# TI_DMM_PCB.net
KiCad netlist of a schematic drawn in EAGLE
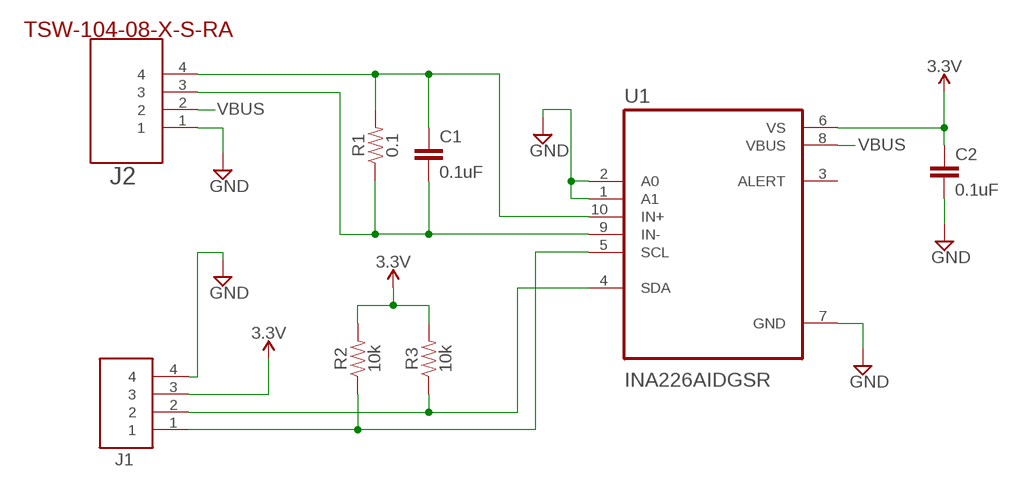
[diagram p0: schematic, sheet 1]

(export (version "E")
  (design (tool "Eeschema 10.0.6"))
  (components
    (comp (ref "C1")
      (value "0.1uF")
      (footprint "eagle-import:0603")
      (libsource (lib "eagle-import") (part "0.1UF-0603"))
    )
    (comp (ref "C2")
      (value "0.1uF")
      (footprint "eagle-import:0603")
      (libsource (lib "eagle-import") (part "0.1UF-0603"))
    )
    (comp (ref "J1")
      (value "4PIN_GROVE_CONNECTOR")
      (footprint "eagle-import:SEEED_114020163")
      (fields (field (name "MF") "Seeed Technology Co., Ltd") (field (name "MP") "110990030"))
      (libsource (lib "eagle-import") (part "4PIN_GROVE_CONNECTOR"))
    )
    (comp (ref "J2")
      (value "TSW-104-08-X-S-RAJ")
      (footprint "eagle-import:SAMTEC-TSW-104-08-X-S-RA")
      (fields (field (name "MF") "Samtec") (field (name "MP") "TSW-104-08-T-S-RA"))
      (libsource (lib "eagle-import") (part "TSW-104-08-X-S-RAJ"))
    )
    (comp (ref "R1")
      (value "0.1")
      (footprint "eagle-import:0603")
      (libsource (lib "eagle-import") (part "0.1OHM"))
    )
    (comp (ref "R2")
      (value "10k")
      (footprint "eagle-import:0603")
      (libsource (lib "eagle-import") (part "10KOHM-0603"))
    )
    (comp (ref "R3")
      (value "10k")
      (footprint "eagle-import:0603")
      (libsource (lib "eagle-import") (part "10KOHM-0603"))
    )
    (comp (ref "U1")
      (value "INA226AIDGSR")
      (footprint "eagle-import:SOP50P490X110-10N")
      (fields (field (name "MF") "Texas Instruments"))
      (libsource (lib "eagle-import") (part "INA226AIDGSR"))
    )
  )
  (nets
    (net (code "1") (name "/VBUS") (class "Default")
      (node (ref "J2") (pin "2") (pinfunction "2_2") (pintype "bidirectional"))
      (node (ref "U1") (pin "8") (pinfunction "VBUS_8") (pintype "power_in"))
    )
    (net (code "2") (name "3.3V") (class "Default")
      (node (ref "C2") (pin "1") (pinfunction "1_1") (pintype "passive"))
      (node (ref "J1") (pin "3") (pinfunction "3_3") (pintype "passive"))
      (node (ref "R2") (pin "2") (pinfunction "2_2") (pintype "passive"))
      (node (ref "R3") (pin "2") (pinfunction "2_2") (pintype "passive"))
      (node (ref "U1") (pin "6") (pinfunction "VS_6") (pintype "power_in"))
    )
    (net (code "3") (name "GND") (class "Default")
      (node (ref "C2") (pin "2") (pinfunction "2_2") (pintype "passive"))
      (node (ref "J1") (pin "4") (pinfunction "4_4") (pintype "passive"))
      (node (ref "J2") (pin "1") (pinfunction "1_1") (pintype "bidirectional"))
      (node (ref "U1") (pin "1") (pinfunction "A1_1") (pintype "input"))
      (node (ref "U1") (pin "2") (pinfunction "A0_2") (pintype "input"))
      (node (ref "U1") (pin "7") (pinfunction "GND_7") (pintype "power_in"))
    )
    (net (code "4") (name "Net-(U1-IN+)") (class "Default")
      (node (ref "C1") (pin "1") (pinfunction "1_1") (pintype "passive"))
      (node (ref "J2") (pin "4") (pinfunction "4_4") (pintype "bidirectional"))
      (node (ref "R1") (pin "2") (pinfunction "2_2") (pintype "passive"))
      (node (ref "U1") (pin "10") (pinfunction "IN+_10") (pintype "input"))
    )
    (net (code "5") (name "Net-(U1-IN-)") (class "Default")
      (node (ref "C1") (pin "2") (pinfunction "2_2") (pintype "passive"))
      (node (ref "J2") (pin "3") (pinfunction "3_3") (pintype "bidirectional"))
      (node (ref "R1") (pin "1") (pinfunction "1_1") (pintype "passive"))
      (node (ref "U1") (pin "9") (pinfunction "IN-_9") (pintype "input"))
    )
    (net (code "6") (name "Net-(U1-SCL)") (class "Default")
      (node (ref "J1") (pin "1") (pinfunction "1_1") (pintype "passive"))
      (node (ref "R2") (pin "1") (pinfunction "1_1") (pintype "passive"))
      (node (ref "U1") (pin "5") (pinfunction "SCL_5") (pintype "input"))
    )
    (net (code "7") (name "Net-(U1-SDA)") (class "Default")
      (node (ref "J1") (pin "2") (pinfunction "2_2") (pintype "passive"))
      (node (ref "R3") (pin "1") (pinfunction "1_1") (pintype "passive"))
      (node (ref "U1") (pin "4") (pinfunction "SDA_4") (pintype "bidirectional"))
    )
    (net (code "8") (name "unconnected-(U1-ALERT-Pad3)") (class "Default")
      (node (ref "U1") (pin "3") (pinfunction "ALERT_3") (pintype "output"))
    )
  )
)
